# NeoPixel.net
KiCad netlist of a schematic drawn in Altium Designer
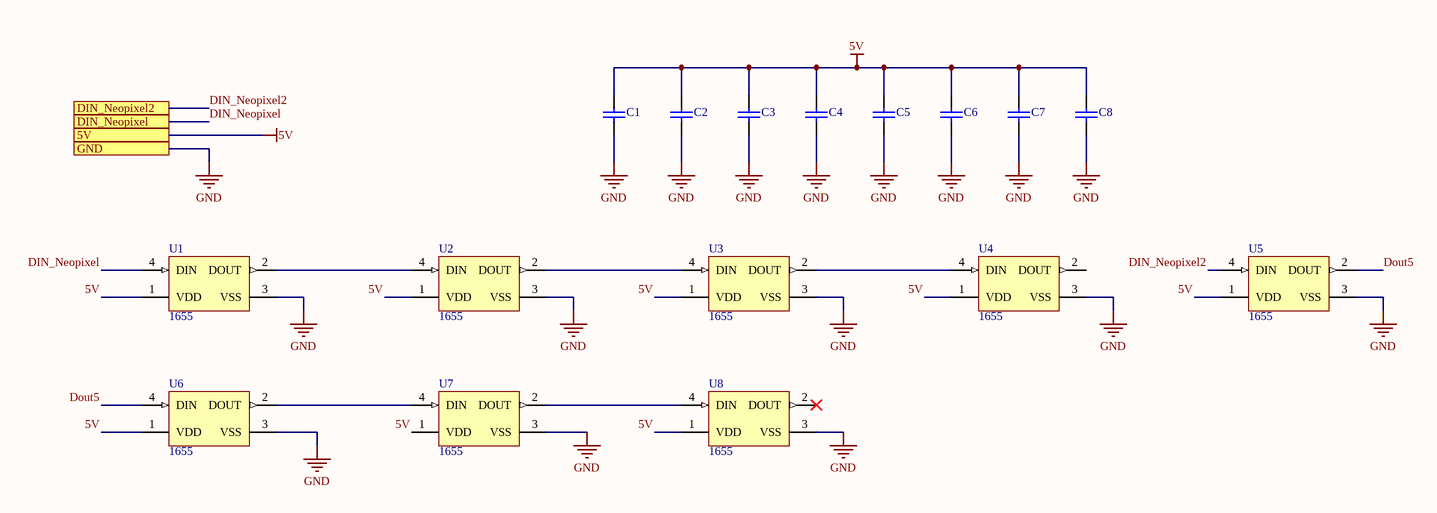
[diagram p0: NeoPixel.SchDoc]

(export (version "E")
  (design (tool "Eeschema 10.0.6"))
  (components
    (comp (ref "C1")
      (value "C0805C105Z4VACTU")
      (footprint "CAPC2013X140X50ML20T25")
      (fields (field (name "MANUFACTURER") "Kemet"))
      (libsource (lib "Altium Content Vault") (part "CAP"))
    )
    (comp (ref "C2")
      (value "C0805C105Z4VACTU")
      (footprint "CAPC2013X140X50ML20T25")
      (fields (field (name "MANUFACTURER") "Kemet"))
      (libsource (lib "Altium Content Vault") (part "CAP"))
    )
    (comp (ref "C3")
      (value "C0805C105Z4VACTU")
      (footprint "CAPC2013X140X50ML20T25")
      (fields (field (name "MANUFACTURER") "Kemet"))
      (libsource (lib "Altium Content Vault") (part "CAP"))
    )
    (comp (ref "C4")
      (value "C0805C105Z4VACTU")
      (footprint "CAPC2013X140X50ML20T25")
      (fields (field (name "MANUFACTURER") "Kemet"))
      (libsource (lib "Altium Content Vault") (part "CAP"))
    )
    (comp (ref "C5")
      (value "C0805C105Z4VACTU")
      (footprint "CAPC2013X140X50ML20T25")
      (fields (field (name "MANUFACTURER") "Kemet"))
      (libsource (lib "Altium Content Vault") (part "CAP"))
    )
    (comp (ref "C6")
      (value "C0805C105Z4VACTU")
      (footprint "CAPC2013X140X50ML20T25")
      (fields (field (name "MANUFACTURER") "Kemet"))
      (libsource (lib "Altium Content Vault") (part "CAP"))
    )
    (comp (ref "C7")
      (value "C0805C105Z4VACTU")
      (footprint "CAPC2013X140X50ML20T25")
      (fields (field (name "MANUFACTURER") "Kemet"))
      (libsource (lib "Altium Content Vault") (part "CAP"))
    )
    (comp (ref "C8")
      (value "C0805C105Z4VACTU")
      (footprint "CAPC2013X140X50ML20T25")
      (fields (field (name "MANUFACTURER") "Kemet"))
      (libsource (lib "Altium Content Vault") (part "CAP"))
    )
    (comp (ref "U1")
      (value "1655")
      (footprint "ADA-RGB-1655_V")
      (fields (field (name "MANUFACTURER") "Adafruit-Industries-LLC"))
      (libsource (lib "Altium Content Vault") (part "ADA-RGB-1655-4"))
    )
    (comp (ref "U2")
      (value "1655")
      (footprint "ADA-RGB-1655_V")
      (fields (field (name "MANUFACTURER") "Adafruit-Industries-LLC"))
      (libsource (lib "Altium Content Vault") (part "ADA-RGB-1655-4"))
    )
    (comp (ref "U3")
      (value "1655")
      (footprint "ADA-RGB-1655_V")
      (fields (field (name "MANUFACTURER") "Adafruit-Industries-LLC"))
      (libsource (lib "Altium Content Vault") (part "ADA-RGB-1655-4"))
    )
    (comp (ref "U4")
      (value "1655")
      (footprint "ADA-RGB-1655_V")
      (fields (field (name "MANUFACTURER") "Adafruit-Industries-LLC"))
      (libsource (lib "Altium Content Vault") (part "ADA-RGB-1655-4"))
    )
    (comp (ref "U5")
      (value "1655")
      (footprint "ADA-RGB-1655_V")
      (fields (field (name "MANUFACTURER") "Adafruit-Industries-LLC"))
      (libsource (lib "Altium Content Vault") (part "ADA-RGB-1655-4"))
    )
    (comp (ref "U6")
      (value "1655")
      (footprint "ADA-RGB-1655_V")
      (fields (field (name "MANUFACTURER") "Adafruit-Industries-LLC"))
      (libsource (lib "Altium Content Vault") (part "ADA-RGB-1655-4"))
    )
    (comp (ref "U7")
      (value "1655")
      (footprint "ADA-RGB-1655_V")
      (fields (field (name "MANUFACTURER") "Adafruit-Industries-LLC"))
      (libsource (lib "Altium Content Vault") (part "ADA-RGB-1655-4"))
    )
    (comp (ref "U8")
      (value "1655")
      (footprint "ADA-RGB-1655_V")
      (fields (field (name "MANUFACTURER") "Adafruit-Industries-LLC"))
      (libsource (lib "Altium Content Vault") (part "ADA-RGB-1655-4"))
    )
  )
  (nets
    (net (code "1") (name "/DIN_Neopixel") (class "Default")
      (node (ref "U1") (pin "4") (pinfunction "DIN_4") (pintype "input"))
    )
    (net (code "2") (name "/DIN_Neopixel2") (class "Default")
      (node (ref "U5") (pin "4") (pinfunction "DIN_4") (pintype "input"))
    )
    (net (code "3") (name "/Dout5") (class "Default")
      (node (ref "U5") (pin "2") (pinfunction "DOUT_2") (pintype "output"))
      (node (ref "U6") (pin "4") (pinfunction "DIN_4") (pintype "input"))
    )
    (net (code "4") (name "5V") (class "Default")
      (node (ref "C1") (pin "2") (pinfunction "2_2") (pintype "passive"))
      (node (ref "C2") (pin "2") (pinfunction "2_2") (pintype "passive"))
      (node (ref "C3") (pin "2") (pinfunction "2_2") (pintype "passive"))
      (node (ref "C4") (pin "2") (pinfunction "2_2") (pintype "passive"))
      (node (ref "C5") (pin "2") (pinfunction "2_2") (pintype "passive"))
      (node (ref "C6") (pin "2") (pinfunction "2_2") (pintype "passive"))
      (node (ref "C7") (pin "2") (pinfunction "2_2") (pintype "passive"))
      (node (ref "C8") (pin "2") (pinfunction "2_2") (pintype "passive"))
      (node (ref "U1") (pin "1") (pinfunction "VDD_1") (pintype "power_in"))
      (node (ref "U2") (pin "1") (pinfunction "VDD_1") (pintype "power_in"))
      (node (ref "U3") (pin "1") (pinfunction "VDD_1") (pintype "power_in"))
      (node (ref "U4") (pin "1") (pinfunction "VDD_1") (pintype "power_in"))
      (node (ref "U5") (pin "1") (pinfunction "VDD_1") (pintype "power_in"))
      (node (ref "U6") (pin "1") (pinfunction "VDD_1") (pintype "power_in"))
      (node (ref "U7") (pin "1") (pinfunction "VDD_1") (pintype "power_in"))
      (node (ref "U8") (pin "1") (pinfunction "VDD_1") (pintype "power_in"))
    )
    (net (code "5") (name "GND") (class "Default")
      (node (ref "C1") (pin "1") (pinfunction "1_1") (pintype "passive"))
      (node (ref "C2") (pin "1") (pinfunction "1_1") (pintype "passive"))
      (node (ref "C3") (pin "1") (pinfunction "1_1") (pintype "passive"))
      (node (ref "C4") (pin "1") (pinfunction "1_1") (pintype "passive"))
      (node (ref "C5") (pin "1") (pinfunction "1_1") (pintype "passive"))
      (node (ref "C6") (pin "1") (pinfunction "1_1") (pintype "passive"))
      (node (ref "C7") (pin "1") (pinfunction "1_1") (pintype "passive"))
      (node (ref "C8") (pin "1") (pinfunction "1_1") (pintype "passive"))
      (node (ref "U1") (pin "3") (pinfunction "VSS_3") (pintype "power_in"))
      (node (ref "U2") (pin "3") (pinfunction "VSS_3") (pintype "power_in"))
      (node (ref "U3") (pin "3") (pinfunction "VSS_3") (pintype "power_in"))
      (node (ref "U4") (pin "3") (pinfunction "VSS_3") (pintype "power_in"))
      (node (ref "U5") (pin "3") (pinfunction "VSS_3") (pintype "power_in"))
      (node (ref "U6") (pin "3") (pinfunction "VSS_3") (pintype "power_in"))
      (node (ref "U7") (pin "3") (pinfunction "VSS_3") (pintype "power_in"))
      (node (ref "U8") (pin "3") (pinfunction "VSS_3") (pintype "power_in"))
    )
    (net (code "6") (name "Net-(U1-DOUT)") (class "Default")
      (node (ref "U1") (pin "2") (pinfunction "DOUT_2") (pintype "output"))
      (node (ref "U2") (pin "4") (pinfunction "DIN_4") (pintype "input"))
    )
    (net (code "7") (name "Net-(U2-DOUT)") (class "Default")
      (node (ref "U2") (pin "2") (pinfunction "DOUT_2") (pintype "output"))
      (node (ref "U3") (pin "4") (pinfunction "DIN_4") (pintype "input"))
    )
    (net (code "8") (name "Net-(U3-DOUT)") (class "Default")
      (node (ref "U3") (pin "2") (pinfunction "DOUT_2") (pintype "output"))
      (node (ref "U4") (pin "4") (pinfunction "DIN_4") (pintype "input"))
    )
    (net (code "9") (name "Net-(U6-DOUT)") (class "Default")
      (node (ref "U6") (pin "2") (pinfunction "DOUT_2") (pintype "output"))
      (node (ref "U7") (pin "4") (pinfunction "DIN_4") (pintype "input"))
    )
    (net (code "10") (name "Net-(U7-DOUT)") (class "Default")
      (node (ref "U7") (pin "2") (pinfunction "DOUT_2") (pintype "output"))
      (node (ref "U8") (pin "4") (pinfunction "DIN_4") (pintype "input"))
    )
    (net (code "11") (name "unconnected-(U4-DOUT-Pad2)") (class "Default")
      (node (ref "U4") (pin "2") (pinfunction "DOUT_2") (pintype "output"))
    )
    (net (code "12") (name "unconnected-(U8-DOUT-Pad2)") (class "Default")
      (node (ref "U8") (pin "2") (pinfunction "DOUT_2") (pintype "output+no_connect"))
    )
  )
)
